# Ampli_FI2.net
KiCad netlist of a schematic drawn in Altium Designer
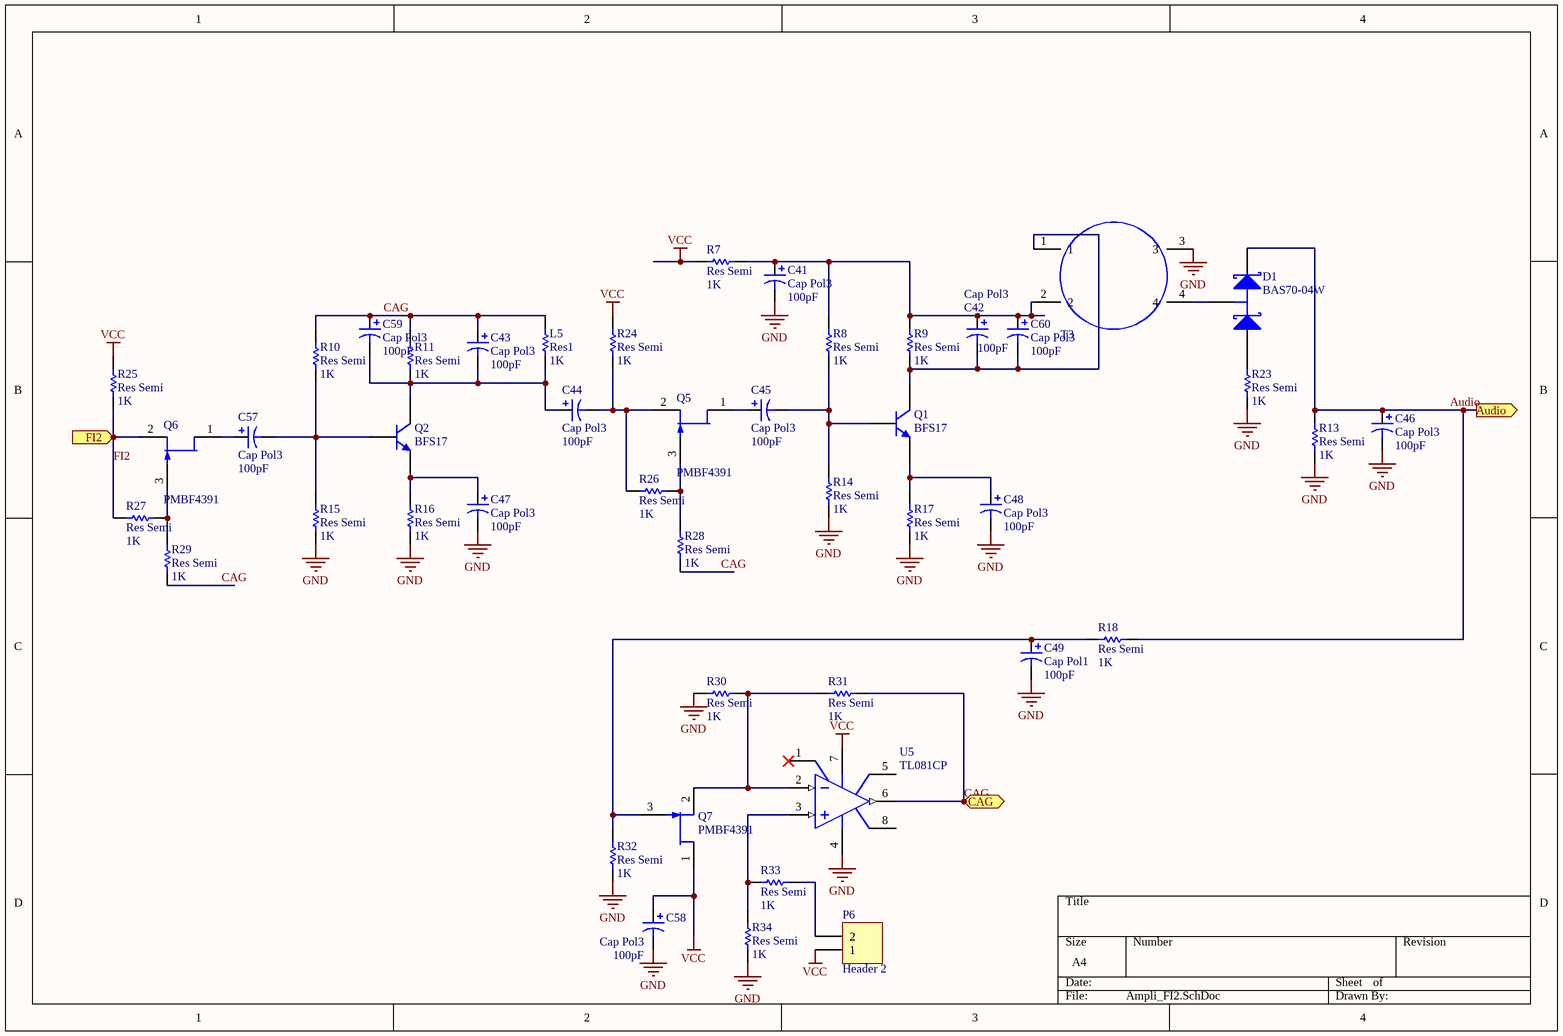
[diagram p0: Ampli_FI2.SchDoc]

(export (version "E")
  (design (tool "Eeschema 10.0.6"))
  (components
    (comp (ref "C41")
      (value "Cap Pol3")
      (footprint "C0805")
      (description "Polarized Capacitor (Surface Mount)")
      (fields (field (name "ALTIUM_VALUE") "100pF") (field (name "PUBLISHER") "Altium Limited"))
      (libsource (lib "Miscellaneous Devices") (part "Cap Pol3"))
    )
    (comp (ref "C42")
      (value "Cap Pol3")
      (footprint "C0805")
      (description "Polarized Capacitor (Surface Mount)")
      (fields (field (name "ALTIUM_VALUE") "100pF") (field (name "PUBLISHER") "Altium Limited"))
      (libsource (lib "Miscellaneous Devices") (part "Cap Pol3"))
    )
    (comp (ref "C43")
      (value "Cap Pol3")
      (footprint "C0805")
      (description "Polarized Capacitor (Surface Mount)")
      (fields (field (name "ALTIUM_VALUE") "100pF") (field (name "PUBLISHER") "Altium Limited"))
      (libsource (lib "Miscellaneous Devices") (part "Cap Pol3"))
    )
    (comp (ref "C44")
      (value "Cap Pol3")
      (footprint "C0805")
      (description "Polarized Capacitor (Surface Mount)")
      (fields (field (name "ALTIUM_VALUE") "100pF") (field (name "PUBLISHER") "Altium Limited"))
      (libsource (lib "Miscellaneous Devices") (part "Cap Pol3"))
    )
    (comp (ref "C45")
      (value "Cap Pol3")
      (footprint "C0805")
      (description "Polarized Capacitor (Surface Mount)")
      (fields (field (name "ALTIUM_VALUE") "100pF") (field (name "PUBLISHER") "Altium Limited"))
      (libsource (lib "Miscellaneous Devices") (part "Cap Pol3"))
    )
    (comp (ref "C46")
      (value "Cap Pol3")
      (footprint "C0805")
      (description "Polarized Capacitor (Surface Mount)")
      (fields (field (name "ALTIUM_VALUE") "100pF") (field (name "PUBLISHER") "Altium Limited"))
      (libsource (lib "Miscellaneous Devices") (part "Cap Pol3"))
    )
    (comp (ref "C47")
      (value "Cap Pol3")
      (footprint "C0805")
      (description "Polarized Capacitor (Surface Mount)")
      (fields (field (name "ALTIUM_VALUE") "100pF") (field (name "PUBLISHER") "Altium Limited"))
      (libsource (lib "Miscellaneous Devices") (part "Cap Pol3"))
    )
    (comp (ref "C48")
      (value "Cap Pol3")
      (footprint "C0805")
      (description "Polarized Capacitor (Surface Mount)")
      (fields (field (name "ALTIUM_VALUE") "100pF") (field (name "PUBLISHER") "Altium Limited"))
      (libsource (lib "Miscellaneous Devices") (part "Cap Pol3"))
    )
    (comp (ref "C49")
      (value "Cap Pol1")
      (footprint "B")
      (description "Polarized Capacitor (Radial)")
      (fields (field (name "ALTIUM_VALUE") "100pF") (field (name "PUBLISHER") "Altium Limited"))
      (libsource (lib "Miscellaneous Devices") (part "Cap Pol1"))
    )
    (comp (ref "C57")
      (value "Cap Pol3")
      (footprint "C0805")
      (description "Polarized Capacitor (Surface Mount)")
      (fields (field (name "ALTIUM_VALUE") "100pF") (field (name "PUBLISHER") "Altium Limited"))
      (libsource (lib "Miscellaneous Devices") (part "Cap Pol3"))
    )
    (comp (ref "C58")
      (value "Cap Pol3")
      (footprint "C0805")
      (description "Polarized Capacitor (Surface Mount)")
      (fields (field (name "ALTIUM_VALUE") "100pF") (field (name "PUBLISHER") "Altium Limited"))
      (libsource (lib "Miscellaneous Devices") (part "Cap Pol3"))
    )
    (comp (ref "C59")
      (value "Cap Pol3")
      (footprint "C0805")
      (description "Polarized Capacitor (Surface Mount)")
      (fields (field (name "ALTIUM_VALUE") "100pF") (field (name "PUBLISHER") "Altium Limited"))
      (libsource (lib "Miscellaneous Devices") (part "Cap Pol3"))
    )
    (comp (ref "C60")
      (value "Cap Pol3")
      (footprint "C0805")
      (description "Polarized Capacitor (Surface Mount)")
      (fields (field (name "ALTIUM_VALUE") "100pF") (field (name "PUBLISHER") "Altium Limited"))
      (libsource (lib "Miscellaneous Devices") (part "Cap Pol3"))
    )
    (comp (ref "D1")
      (value "BAS70-04W")
      (footprint "SOT323_N")
      (description "Schottky Barrier Double Diode")
      (fields (field (name "PUBLISHER") "Altium Limited"))
      (libsource (lib "Philips Discrete Diode - Schottky") (part "BAS70-04W"))
    )
    (comp (ref "L5")
      (value "Res1")
      (footprint "AXIAL-0.3")
      (description "Resistor")
      (fields (field (name "ALTIUM_VALUE") "1K") (field (name "PUBLISHER") "Altium Limited"))
      (libsource (lib "Miscellaneous Devices") (part "Res1"))
    )
    (comp (ref "P6")
      (value "Header 2")
      (footprint "HDR1X2")
      (description "Header, 2-Pin")
      (fields (field (name "PUBLISHER") "Altium Limited"))
      (libsource (lib "Miscellaneous Connectors") (part "Header 2"))
    )
    (comp (ref "Q1")
      (value "BFS17")
      (footprint "SOT23_N")
      (description "NPN 1 GHz Wideband Transistor")
      (fields (field (name "PUBLISHER") "Altium Limited"))
      (libsource (lib "Philips Discrete BJT - RF Transistor") (part "BFS17"))
    )
    (comp (ref "Q2")
      (value "BFS17")
      (footprint "SOT23_N")
      (description "NPN 1 GHz Wideband Transistor")
      (fields (field (name "PUBLISHER") "Altium Limited"))
      (libsource (lib "Philips Discrete BJT - RF Transistor") (part "BFS17"))
    )
    (comp (ref "Q5")
      (value "PMBF4391")
      (footprint "SOT23_N")
      (description "N-channel Silicon Junction Field-effect Transistor")
      (fields (field (name "PUBLISHER") "Altium Limited"))
      (libsource (lib "Philips Discrete JFET") (part "PMBF4391"))
    )
    (comp (ref "Q6")
      (value "PMBF4391")
      (footprint "SOT23_N")
      (description "N-channel Silicon Junction Field-effect Transistor")
      (fields (field (name "PUBLISHER") "Altium Limited"))
      (libsource (lib "Philips Discrete JFET") (part "PMBF4391"))
    )
    (comp (ref "Q7")
      (value "PMBF4391")
      (footprint "SOT23_N")
      (description "N-channel Silicon Junction Field-effect Transistor")
      (fields (field (name "PUBLISHER") "Altium Limited"))
      (libsource (lib "Philips Discrete JFET") (part "PMBF4391"))
    )
    (comp (ref "R7")
      (value "Res Semi")
      (footprint "2012[0805]")
      (description "Semiconductor Resistor")
      (fields (field (name "ALTIUM_VALUE") "1K") (field (name "PUBLISHER") "Altium Limited"))
      (libsource (lib "Miscellaneous Devices") (part "Res Semi"))
    )
    (comp (ref "R8")
      (value "Res Semi")
      (footprint "2012[0805]")
      (description "Semiconductor Resistor")
      (fields (field (name "ALTIUM_VALUE") "1K") (field (name "PUBLISHER") "Altium Limited"))
      (libsource (lib "Miscellaneous Devices") (part "Res Semi"))
    )
    (comp (ref "R9")
      (value "Res Semi")
      (footprint "2012[0805]")
      (description "Semiconductor Resistor")
      (fields (field (name "ALTIUM_VALUE") "1K") (field (name "PUBLISHER") "Altium Limited"))
      (libsource (lib "Miscellaneous Devices") (part "Res Semi"))
    )
    (comp (ref "R10")
      (value "Res Semi")
      (footprint "2012[0805]")
      (description "Semiconductor Resistor")
      (fields (field (name "ALTIUM_VALUE") "1K") (field (name "PUBLISHER") "Altium Limited"))
      (libsource (lib "Miscellaneous Devices") (part "Res Semi"))
    )
    (comp (ref "R11")
      (value "Res Semi")
      (footprint "2012[0805]")
      (description "Semiconductor Resistor")
      (fields (field (name "ALTIUM_VALUE") "1K") (field (name "PUBLISHER") "Altium Limited"))
      (libsource (lib "Miscellaneous Devices") (part "Res Semi"))
    )
    (comp (ref "R13")
      (value "Res Semi")
      (footprint "2012[0805]")
      (description "Semiconductor Resistor")
      (fields (field (name "ALTIUM_VALUE") "1K") (field (name "PUBLISHER") "Altium Limited"))
      (libsource (lib "Miscellaneous Devices") (part "Res Semi"))
    )
    (comp (ref "R14")
      (value "Res Semi")
      (footprint "2012[0805]")
      (description "Semiconductor Resistor")
      (fields (field (name "ALTIUM_VALUE") "1K") (field (name "PUBLISHER") "Altium Limited"))
      (libsource (lib "Miscellaneous Devices") (part "Res Semi"))
    )
    (comp (ref "R15")
      (value "Res Semi")
      (footprint "2012[0805]")
      (description "Semiconductor Resistor")
      (fields (field (name "ALTIUM_VALUE") "1K") (field (name "PUBLISHER") "Altium Limited"))
      (libsource (lib "Miscellaneous Devices") (part "Res Semi"))
    )
    (comp (ref "R16")
      (value "Res Semi")
      (footprint "2012[0805]")
      (description "Semiconductor Resistor")
      (fields (field (name "ALTIUM_VALUE") "1K") (field (name "PUBLISHER") "Altium Limited"))
      (libsource (lib "Miscellaneous Devices") (part "Res Semi"))
    )
    (comp (ref "R17")
      (value "Res Semi")
      (footprint "2012[0805]")
      (description "Semiconductor Resistor")
      (fields (field (name "ALTIUM_VALUE") "1K") (field (name "PUBLISHER") "Altium Limited"))
      (libsource (lib "Miscellaneous Devices") (part "Res Semi"))
    )
    (comp (ref "R18")
      (value "Res Semi")
      (footprint "2012[0805]")
      (description "Semiconductor Resistor")
      (fields (field (name "ALTIUM_VALUE") "1K") (field (name "PUBLISHER") "Altium Limited"))
      (libsource (lib "Miscellaneous Devices") (part "Res Semi"))
    )
    (comp (ref "R23")
      (value "Res Semi")
      (footprint "2012[0805]")
      (description "Semiconductor Resistor")
      (fields (field (name "ALTIUM_VALUE") "1K") (field (name "PUBLISHER") "Altium Limited"))
      (libsource (lib "Miscellaneous Devices") (part "Res Semi"))
    )
    (comp (ref "R24")
      (value "Res Semi")
      (footprint "2012[0805]")
      (description "Semiconductor Resistor")
      (fields (field (name "ALTIUM_VALUE") "1K") (field (name "PUBLISHER") "Altium Limited"))
      (libsource (lib "Miscellaneous Devices") (part "Res Semi"))
    )
    (comp (ref "R25")
      (value "Res Semi")
      (footprint "2012[0805]")
      (description "Semiconductor Resistor")
      (fields (field (name "ALTIUM_VALUE") "1K") (field (name "PUBLISHER") "Altium Limited"))
      (libsource (lib "Miscellaneous Devices") (part "Res Semi"))
    )
    (comp (ref "R26")
      (value "Res Semi")
      (footprint "2012[0805]")
      (description "Semiconductor Resistor")
      (fields (field (name "ALTIUM_VALUE") "1K") (field (name "PUBLISHER") "Altium Limited"))
      (libsource (lib "Miscellaneous Devices") (part "Res Semi"))
    )
    (comp (ref "R27")
      (value "Res Semi")
      (footprint "2012[0805]")
      (description "Semiconductor Resistor")
      (fields (field (name "ALTIUM_VALUE") "1K") (field (name "PUBLISHER") "Altium Limited"))
      (libsource (lib "Miscellaneous Devices") (part "Res Semi"))
    )
    (comp (ref "R28")
      (value "Res Semi")
      (footprint "2012[0805]")
      (description "Semiconductor Resistor")
      (fields (field (name "ALTIUM_VALUE") "1K") (field (name "PUBLISHER") "Altium Limited"))
      (libsource (lib "Miscellaneous Devices") (part "Res Semi"))
    )
    (comp (ref "R29")
      (value "Res Semi")
      (footprint "2012[0805]")
      (description "Semiconductor Resistor")
      (fields (field (name "ALTIUM_VALUE") "1K") (field (name "PUBLISHER") "Altium Limited"))
      (libsource (lib "Miscellaneous Devices") (part "Res Semi"))
    )
    (comp (ref "R30")
      (value "Res Semi")
      (footprint "2012[0805]")
      (description "Semiconductor Resistor")
      (fields (field (name "ALTIUM_VALUE") "1K") (field (name "PUBLISHER") "Altium Limited"))
      (libsource (lib "Miscellaneous Devices") (part "Res Semi"))
    )
    (comp (ref "R31")
      (value "Res Semi")
      (footprint "2012[0805]")
      (description "Semiconductor Resistor")
      (fields (field (name "ALTIUM_VALUE") "1K") (field (name "PUBLISHER") "Altium Limited"))
      (libsource (lib "Miscellaneous Devices") (part "Res Semi"))
    )
    (comp (ref "R32")
      (value "Res Semi")
      (footprint "2012[0805]")
      (description "Semiconductor Resistor")
      (fields (field (name "ALTIUM_VALUE") "1K") (field (name "PUBLISHER") "Altium Limited"))
      (libsource (lib "Miscellaneous Devices") (part "Res Semi"))
    )
    (comp (ref "R33")
      (value "Res Semi")
      (footprint "2012[0805]")
      (description "Semiconductor Resistor")
      (fields (field (name "ALTIUM_VALUE") "1K") (field (name "PUBLISHER") "Altium Limited"))
      (libsource (lib "Miscellaneous Devices") (part "Res Semi"))
    )
    (comp (ref "R34")
      (value "Res Semi")
      (footprint "2012[0805]")
      (description "Semiconductor Resistor")
      (fields (field (name "ALTIUM_VALUE") "1K") (field (name "PUBLISHER") "Altium Limited"))
      (libsource (lib "Miscellaneous Devices") (part "Res Semi"))
    )
    (comp (ref "T3")
      (value "Toroide")
      (footprint "NTH12_4")
      (libsource (lib "epf") (part "Transformador_Toroide"))
    )
    (comp (ref "U5")
      (value "TL081CP")
      (footprint "626-05")
      (description "JFET-Input Operational Amplifier")
      (fields (field (name "PUBLISHER") "Altium Limited"))
      (libsource (lib "Motorola Amplifier Operational Amplifier") (part "TL081CP"))
    )
  )
  (nets
    (net (code "1") (name "/Audio") (class "Default")
      (node (ref "C46") (pin "1") (pinfunction "1_1") (pintype "passive"))
      (node (ref "D1") (pin "2") (pinfunction "K_2") (pintype "passive"))
      (node (ref "R13") (pin "2") (pinfunction "2_2") (pintype "passive"))
      (node (ref "R18") (pin "1") (pinfunction "1_1") (pintype "passive"))
    )
    (net (code "2") (name "/CAG") (class "Default")
      (node (ref "C43") (pin "1") (pinfunction "1_1") (pintype "passive"))
      (node (ref "C59") (pin "1") (pinfunction "1_1") (pintype "passive"))
      (node (ref "L5") (pin "2") (pinfunction "2_2") (pintype "passive"))
      (node (ref "R10") (pin "2") (pinfunction "2_2") (pintype "passive"))
      (node (ref "R11") (pin "2") (pinfunction "2_2") (pintype "passive"))
      (node (ref "R28") (pin "2") (pinfunction "2_2") (pintype "passive"))
      (node (ref "R29") (pin "2") (pinfunction "2_2") (pintype "passive"))
      (node (ref "R31") (pin "2") (pinfunction "2_2") (pintype "passive"))
      (node (ref "U5") (pin "6") (pinfunction "OUT_6") (pintype "output"))
    )
    (net (code "3") (name "/FI2") (class "Default")
      (node (ref "Q6") (pin "2") (pinfunction "S_2") (pintype "passive"))
      (node (ref "R25") (pin "2") (pinfunction "2_2") (pintype "passive"))
      (node (ref "R27") (pin "1") (pinfunction "1_1") (pintype "passive"))
    )
    (net (code "4") (name "GND") (class "Default")
      (node (ref "C41") (pin "2") (pinfunction "2_2") (pintype "passive"))
      (node (ref "C46") (pin "2") (pinfunction "2_2") (pintype "passive"))
      (node (ref "C47") (pin "2") (pinfunction "2_2") (pintype "passive"))
      (node (ref "C48") (pin "2") (pinfunction "2_2") (pintype "passive"))
      (node (ref "C49") (pin "2") (pinfunction "2_2") (pintype "passive"))
      (node (ref "C58") (pin "2") (pinfunction "2_2") (pintype "passive"))
      (node (ref "R13") (pin "1") (pinfunction "1_1") (pintype "passive"))
      (node (ref "R14") (pin "2") (pinfunction "2_2") (pintype "passive"))
      (node (ref "R15") (pin "1") (pinfunction "1_1") (pintype "passive"))
      (node (ref "R16") (pin "1") (pinfunction "1_1") (pintype "passive"))
      (node (ref "R17") (pin "2") (pinfunction "2_2") (pintype "passive"))
      (node (ref "R23") (pin "1") (pinfunction "1_1") (pintype "passive"))
      (node (ref "R30") (pin "1") (pinfunction "1_1") (pintype "passive"))
      (node (ref "R32") (pin "2") (pinfunction "2_2") (pintype "passive"))
      (node (ref "R34") (pin "2") (pinfunction "2_2") (pintype "passive"))
      (node (ref "T3") (pin "3") (pinfunction "3_3") (pintype "passive"))
      (node (ref "U5") (pin "4") (pinfunction "V-_4") (pintype "power_in"))
    )
    (net (code "5") (name "Net-(C41-Pad1)") (class "Default")
      (node (ref "C41") (pin "1") (pinfunction "1_1") (pintype "passive"))
      (node (ref "C42") (pin "1") (pinfunction "1_1") (pintype "passive"))
      (node (ref "C60") (pin "1") (pinfunction "1_1") (pintype "passive"))
      (node (ref "R7") (pin "1") (pinfunction "1_1") (pintype "passive"))
      (node (ref "R8") (pin "1") (pinfunction "1_1") (pintype "passive"))
      (node (ref "R9") (pin "1") (pinfunction "1_1") (pintype "passive"))
      (node (ref "T3") (pin "2") (pinfunction "2_2") (pintype "passive"))
    )
    (net (code "6") (name "Net-(D1-A)") (class "Default")
      (node (ref "D1") (pin "1") (pinfunction "A_1") (pintype "passive"))
      (node (ref "R23") (pin "2") (pinfunction "2_2") (pintype "passive"))
    )
    (net (code "7") (name "Net-(D1-C)") (class "Default")
      (node (ref "D1") (pin "3") (pinfunction "C_3") (pintype "passive"))
      (node (ref "T3") (pin "4") (pinfunction "4_4") (pintype "passive"))
    )
    (net (code "8") (name "Net-(P6-Pad2)") (class "Default")
      (node (ref "P6") (pin "2") (pinfunction "2_2") (pintype "passive"))
      (node (ref "R33") (pin "1") (pinfunction "1_1") (pintype "passive"))
    )
    (net (code "9") (name "Net-(Q1-B)") (class "Default")
      (node (ref "C45") (pin "2") (pinfunction "2_2") (pintype "passive"))
      (node (ref "Q1") (pin "1") (pinfunction "B_1") (pintype "passive"))
      (node (ref "R14") (pin "1") (pinfunction "1_1") (pintype "passive"))
      (node (ref "R8") (pin "2") (pinfunction "2_2") (pintype "passive"))
    )
    (net (code "10") (name "Net-(Q1-C)") (class "Default")
      (node (ref "C42") (pin "2") (pinfunction "2_2") (pintype "passive"))
      (node (ref "C60") (pin "2") (pinfunction "2_2") (pintype "passive"))
      (node (ref "Q1") (pin "3") (pinfunction "C_3") (pintype "passive"))
      (node (ref "R9") (pin "2") (pinfunction "2_2") (pintype "passive"))
      (node (ref "T3") (pin "1") (pinfunction "1_1") (pintype "passive"))
    )
    (net (code "11") (name "Net-(Q1-E)") (class "Default")
      (node (ref "C48") (pin "1") (pinfunction "1_1") (pintype "passive"))
      (node (ref "Q1") (pin "2") (pinfunction "E_2") (pintype "passive"))
      (node (ref "R17") (pin "1") (pinfunction "1_1") (pintype "passive"))
    )
    (net (code "12") (name "Net-(Q2-B)") (class "Default")
      (node (ref "C57") (pin "2") (pinfunction "2_2") (pintype "passive"))
      (node (ref "Q2") (pin "1") (pinfunction "B_1") (pintype "passive"))
      (node (ref "R10") (pin "1") (pinfunction "1_1") (pintype "passive"))
      (node (ref "R15") (pin "2") (pinfunction "2_2") (pintype "passive"))
    )
    (net (code "13") (name "Net-(Q2-C)") (class "Default")
      (node (ref "C43") (pin "2") (pinfunction "2_2") (pintype "passive"))
      (node (ref "C44") (pin "1") (pinfunction "1_1") (pintype "passive"))
      (node (ref "C59") (pin "2") (pinfunction "2_2") (pintype "passive"))
      (node (ref "L5") (pin "1") (pinfunction "1_1") (pintype "passive"))
      (node (ref "Q2") (pin "3") (pinfunction "C_3") (pintype "passive"))
      (node (ref "R11") (pin "1") (pinfunction "1_1") (pintype "passive"))
    )
    (net (code "14") (name "Net-(Q2-E)") (class "Default")
      (node (ref "C47") (pin "1") (pinfunction "1_1") (pintype "passive"))
      (node (ref "Q2") (pin "2") (pinfunction "E_2") (pintype "passive"))
      (node (ref "R16") (pin "2") (pinfunction "2_2") (pintype "passive"))
    )
    (net (code "15") (name "Net-(Q5-D)") (class "Default")
      (node (ref "C45") (pin "1") (pinfunction "1_1") (pintype "passive"))
      (node (ref "Q5") (pin "1") (pinfunction "D_1") (pintype "passive"))
    )
    (net (code "16") (name "Net-(Q5-G)") (class "Default")
      (node (ref "Q5") (pin "3") (pinfunction "G_3") (pintype "passive"))
      (node (ref "R26") (pin "2") (pinfunction "2_2") (pintype "passive"))
      (node (ref "R28") (pin "1") (pinfunction "1_1") (pintype "passive"))
    )
    (net (code "17") (name "Net-(Q5-S)") (class "Default")
      (node (ref "C44") (pin "2") (pinfunction "2_2") (pintype "passive"))
      (node (ref "Q5") (pin "2") (pinfunction "S_2") (pintype "passive"))
      (node (ref "R24") (pin "1") (pinfunction "1_1") (pintype "passive"))
      (node (ref "R26") (pin "1") (pinfunction "1_1") (pintype "passive"))
    )
    (net (code "18") (name "Net-(Q6-D)") (class "Default")
      (node (ref "C57") (pin "1") (pinfunction "1_1") (pintype "passive"))
      (node (ref "Q6") (pin "1") (pinfunction "D_1") (pintype "passive"))
    )
    (net (code "19") (name "Net-(Q6-G)") (class "Default")
      (node (ref "Q6") (pin "3") (pinfunction "G_3") (pintype "passive"))
      (node (ref "R27") (pin "2") (pinfunction "2_2") (pintype "passive"))
      (node (ref "R29") (pin "1") (pinfunction "1_1") (pintype "passive"))
    )
    (net (code "20") (name "Net-(Q7-G)") (class "Default")
      (node (ref "C49") (pin "1") (pinfunction "1_1") (pintype "passive"))
      (node (ref "Q7") (pin "3") (pinfunction "G_3") (pintype "passive"))
      (node (ref "R18") (pin "2") (pinfunction "2_2") (pintype "passive"))
      (node (ref "R32") (pin "1") (pinfunction "1_1") (pintype "passive"))
    )
    (net (code "21") (name "Net-(Q7-S)") (class "Default")
      (node (ref "Q7") (pin "2") (pinfunction "S_2") (pintype "passive"))
      (node (ref "R30") (pin "2") (pinfunction "2_2") (pintype "passive"))
      (node (ref "R31") (pin "1") (pinfunction "1_1") (pintype "passive"))
      (node (ref "U5") (pin "2") (pinfunction "IN-_2") (pintype "input"))
    )
    (net (code "22") (name "Net-(U5-IN+)") (class "Default")
      (node (ref "R33") (pin "2") (pinfunction "2_2") (pintype "passive"))
      (node (ref "R34") (pin "1") (pinfunction "1_1") (pintype "passive"))
      (node (ref "U5") (pin "3") (pinfunction "IN+_3") (pintype "input"))
    )
    (net (code "23") (name "VCC") (class "Default")
      (node (ref "C58") (pin "1") (pinfunction "1_1") (pintype "passive"))
      (node (ref "P6") (pin "1") (pinfunction "1_1") (pintype "passive"))
      (node (ref "Q7") (pin "1") (pinfunction "D_1") (pintype "passive"))
      (node (ref "R24") (pin "2") (pinfunction "2_2") (pintype "passive"))
      (node (ref "R25") (pin "1") (pinfunction "1_1") (pintype "passive"))
      (node (ref "R7") (pin "2") (pinfunction "2_2") (pintype "passive"))
      (node (ref "U5") (pin "7") (pinfunction "V+_7") (pintype "power_in"))
    )
    (net (code "24") (name "unconnected-(U5-NC-Pad8)") (class "Default")
      (node (ref "U5") (pin "8") (pinfunction "NC_8") (pintype "passive"))
    )
    (net (code "25") (name "unconnected-(U5-OS_NULL-Pad1)") (class "Default")
      (node (ref "U5") (pin "1") (pinfunction "OS_NULL_1") (pintype "passive+no_connect"))
    )
    (net (code "26") (name "unconnected-(U5-OS_NULL-Pad5)") (class "Default")
      (node (ref "U5") (pin "5") (pinfunction "OS_NULL_5") (pintype "passive"))
    )
  )
)
